# Adafruit_VEML6070.net
KiCad netlist of a schematic drawn in EAGLE
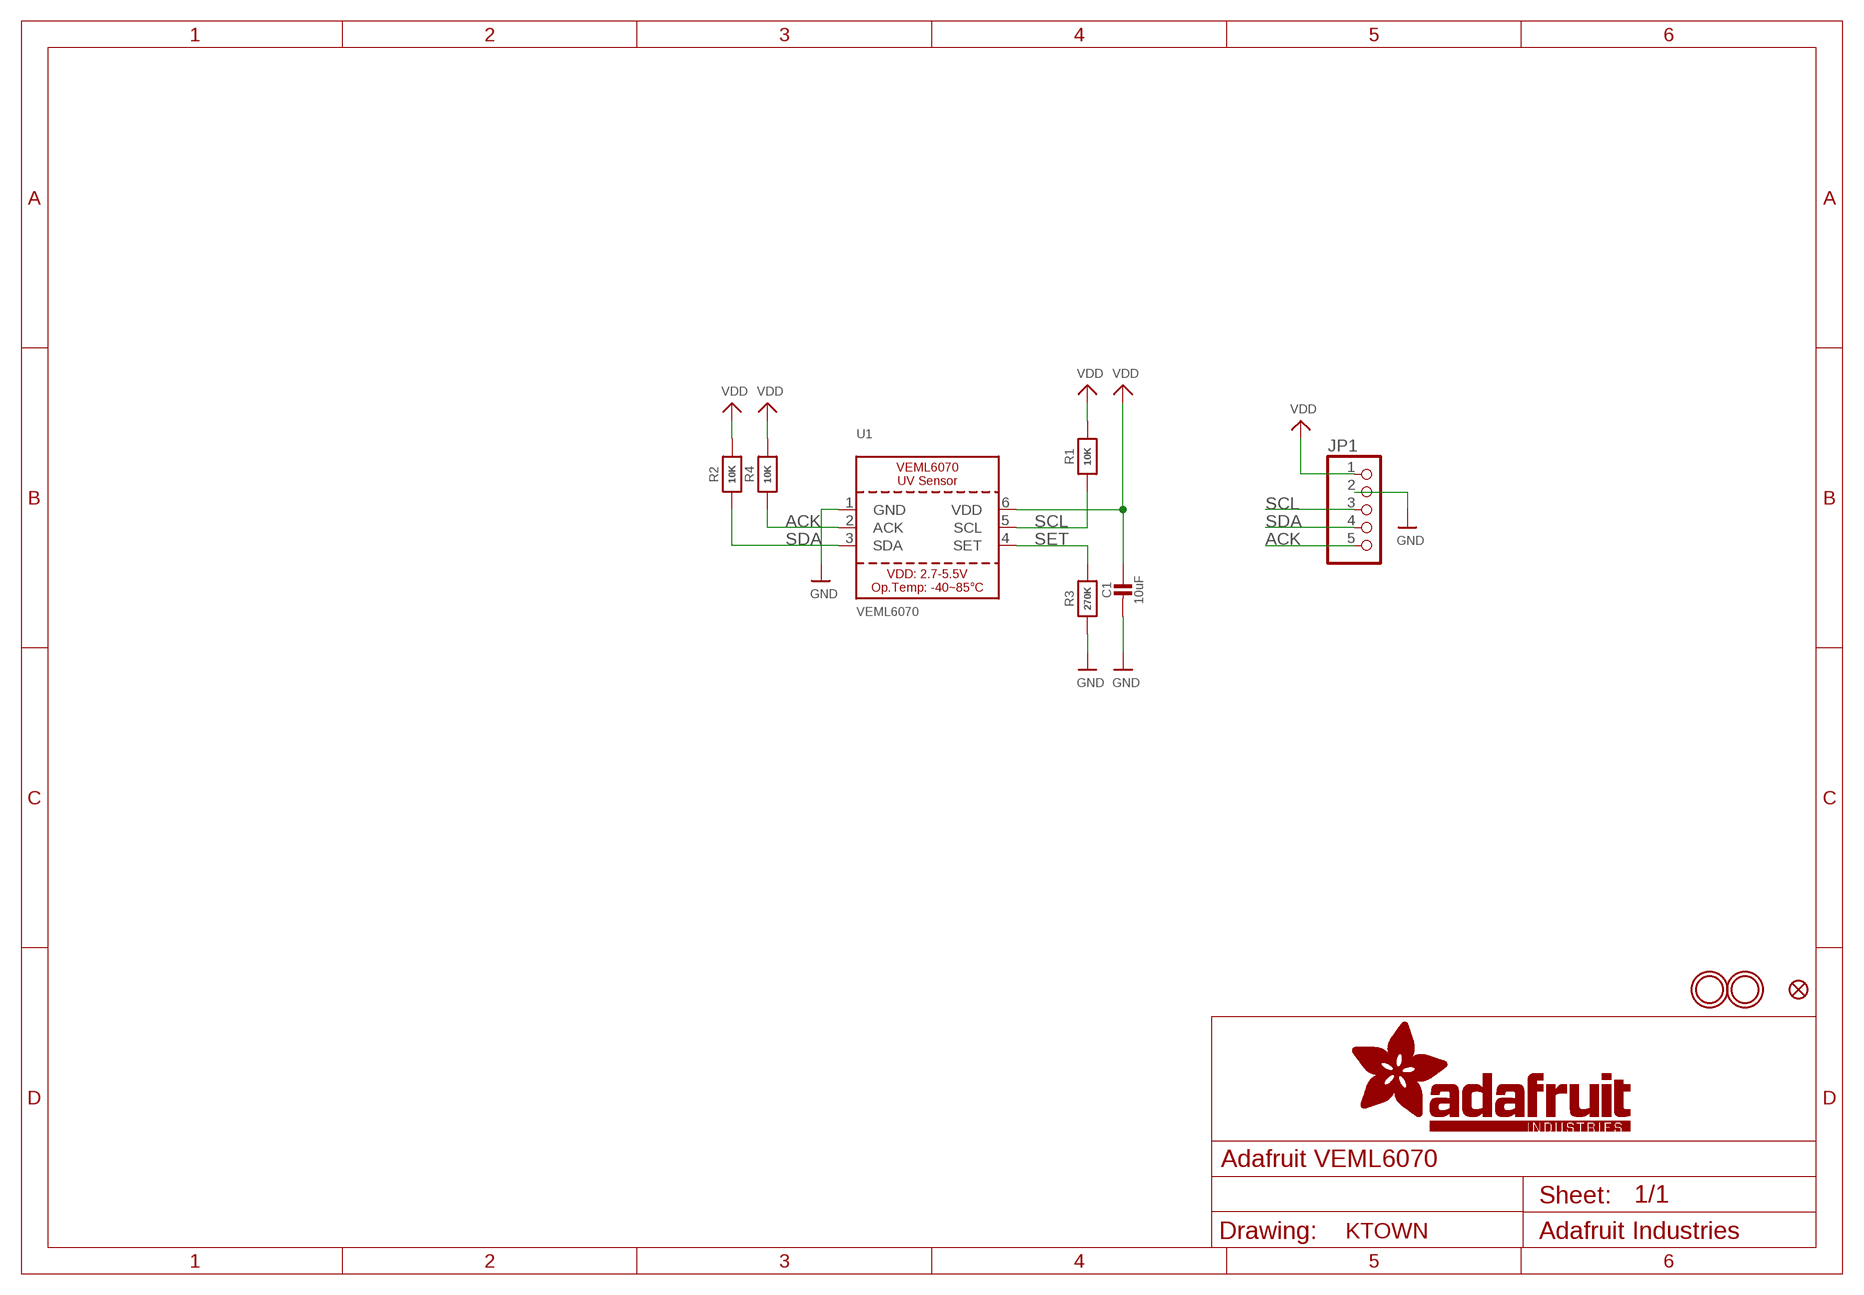
[diagram p0: schematic, sheet 1]

(export (version "E")
  (design (tool "Eeschema 10.0.6"))
  (components
    (comp (ref "C1")
      (value "10uF")
      (footprint "eagle-import:0805-NO")
      (libsource (lib "eagle-import") (part "CAP_CERAMIC0805-NOOUTLINE"))
    )
    (comp (ref "FID1")
      (value "FIDUCIAL\"\"")
      (footprint "eagle-import:FIDUCIAL_1MM")
      (libsource (lib "eagle-import") (part "FIDUCIAL{dblquote}{dblquote}"))
    )
    (comp (ref "JP1")
      (value "HEADER-1X570MIL")
      (footprint "eagle-import:1X05_ROUND_70")
      (libsource (lib "eagle-import") (part "HEADER-1X570MIL"))
    )
    (comp (ref "R1")
      (value "10K")
      (footprint "eagle-import:0805-NO")
      (libsource (lib "eagle-import") (part "RESISTOR0805_NOOUTLINE"))
    )
    (comp (ref "R2")
      (value "10K")
      (footprint "eagle-import:0805-NO")
      (libsource (lib "eagle-import") (part "RESISTOR0805_NOOUTLINE"))
    )
    (comp (ref "R3")
      (value "270K")
      (footprint "eagle-import:0805-NO")
      (libsource (lib "eagle-import") (part "RESISTOR0805_NOOUTLINE"))
    )
    (comp (ref "R4")
      (value "10K")
      (footprint "eagle-import:0805-NO")
      (libsource (lib "eagle-import") (part "RESISTOR0805_NOOUTLINE"))
    )
    (comp (ref "U$10")
      (value "MOUNTINGHOLE2.5")
      (footprint "eagle-import:MOUNTINGHOLE_2.5_PLATED")
      (libsource (lib "eagle-import") (part "MOUNTINGHOLE2.5"))
    )
    (comp (ref "U$11")
      (value "MOUNTINGHOLE2.5")
      (footprint "eagle-import:MOUNTINGHOLE_2.5_PLATED")
      (libsource (lib "eagle-import") (part "MOUNTINGHOLE2.5"))
    )
    (comp (ref "U1")
      (value "VEML6070")
      (footprint "eagle-import:VEML6070")
      (libsource (lib "eagle-import") (part "UV_VEML6070"))
    )
  )
  (nets
    (net (code "1") (name "/ACK") (class "Default")
      (node (ref "JP1") (pin "5") (pinfunction "5_5") (pintype "passive"))
      (node (ref "R4") (pin "1") (pinfunction "1_1") (pintype "passive"))
      (node (ref "U1") (pin "2") (pinfunction "ACK_2") (pintype "open_collector"))
    )
    (net (code "2") (name "/SCL") (class "Default")
      (node (ref "JP1") (pin "3") (pinfunction "3_3") (pintype "passive"))
      (node (ref "R1") (pin "1") (pinfunction "1_1") (pintype "passive"))
      (node (ref "U1") (pin "5") (pinfunction "SCL_5") (pintype "input"))
    )
    (net (code "3") (name "/SDA") (class "Default")
      (node (ref "JP1") (pin "4") (pinfunction "4_4") (pintype "passive"))
      (node (ref "R2") (pin "1") (pinfunction "1_1") (pintype "passive"))
      (node (ref "U1") (pin "3") (pinfunction "SDA_3") (pintype "open_collector"))
    )
    (net (code "4") (name "/SET") (class "Default")
      (node (ref "R3") (pin "2") (pinfunction "2_2") (pintype "passive"))
      (node (ref "U1") (pin "4") (pinfunction "SET_4") (pintype "passive"))
    )
    (net (code "5") (name "GND") (class "Default")
      (node (ref "C1") (pin "2") (pinfunction "2_2") (pintype "passive"))
      (node (ref "JP1") (pin "2") (pinfunction "2_2") (pintype "passive"))
      (node (ref "R3") (pin "1") (pinfunction "1_1") (pintype "passive"))
      (node (ref "U1") (pin "1") (pinfunction "GND_1") (pintype "power_in"))
    )
    (net (code "6") (name "VDD") (class "Default")
      (node (ref "C1") (pin "1") (pinfunction "1_1") (pintype "passive"))
      (node (ref "JP1") (pin "1") (pinfunction "1_1") (pintype "passive"))
      (node (ref "R1") (pin "2") (pinfunction "2_2") (pintype "passive"))
      (node (ref "R2") (pin "2") (pinfunction "2_2") (pintype "passive"))
      (node (ref "R4") (pin "2") (pinfunction "2_2") (pintype "passive"))
      (node (ref "U1") (pin "6") (pinfunction "VDD_6") (pintype "power_in"))
    )
  )
)
